# LCD_Character_2x16.net
KiCad netlist of a schematic drawn in Altium Designer
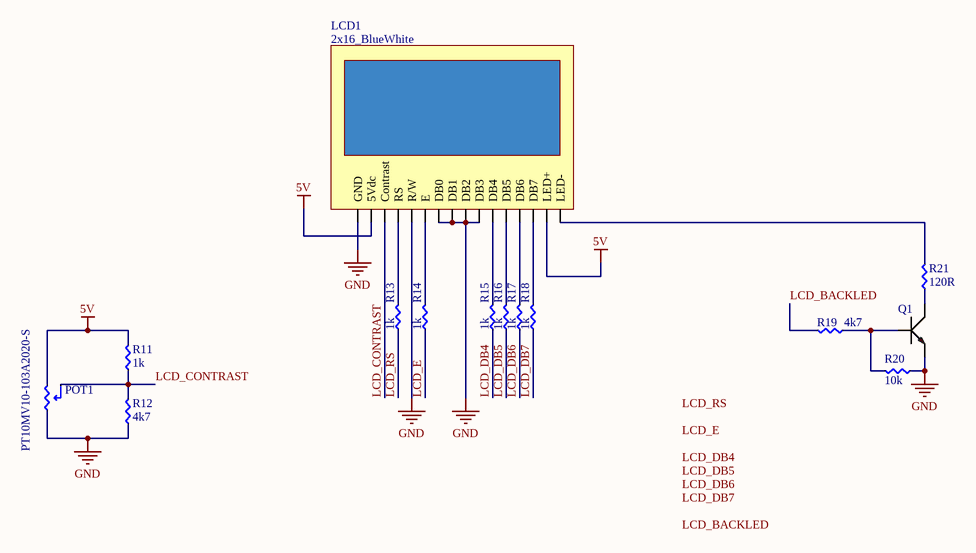
[diagram p0: LCD_Character_2x16.SchDoc]

(export (version "E")
  (design (tool "Eeschema 10.0.6"))
  (components
    (comp (ref "LCD1")
      (value "2x16_BlueWhite")
      (footprint "LCD_2x16_8.4mm")
      (description "LCD MOD CHAR 2X16 WHT TRANSM")
      (fields
        (field (name "MANUFACTURER") "Newhaven Display")
        (field (name "MANUFACTURER PART NUMBER") "NHD-0216K1Z-NSW-BBW-L")
      )
      (libsource (lib "SEMATIK_LIB") (part "NHD-0216K1Z-NSW-BBW-L"))
    )
    (comp (ref "POT1")
      (value "PT10MV10-103A2020-S")
      (footprint "pot_piher_v10")
      (description "POT 10K OHM LINEAR")
      (libsource (lib "SEMATIK_LIB") (part "PT10MV10-103A2020-S"))
    )
    (comp (ref "Q1")
      (value "BC817-25LT1G")
      (footprint "SOT-23")
      (description "TRANS NPN 45V 0.5A SOT23")
      (fields (field (name "MANUFACTURER") "ON Semiconductor") (field (name "BASE PART NUMBER") "BC817"))
      (libsource (lib "SEMATIK_LIB") (part "BC817-25LT1G"))
    )
    (comp (ref "R11")
      (value "1k")
      (footprint "R_0805")
      (description "RES SMD 1K OHM 5% 1/8W 0805")
      (fields (field (name "TOLERANCE") "5%"))
      (libsource (lib "SEMATIK_LIB") (part "RC0805JR-071KL"))
    )
    (comp (ref "R12")
      (value "4k7")
      (footprint "R_0805")
      (description "RES SMD 4.7K OHM 5% 1/8W 0805")
      (fields
        (field (name "MANUFACTURER") "Yageo")
        (field (name "MANUFACTURER PART NUMBER") "RC0805JR-074K7L")
      )
      (libsource (lib "SEMATIK_LIB") (part "RC0805JR-074K7L"))
    )
    (comp (ref "R13")
      (value "1k")
      (footprint "R_0805")
      (description "RES SMD 1K OHM 5% 1/8W 0805")
      (fields (field (name "TOLERANCE") "5%"))
      (libsource (lib "SEMATIK_LIB") (part "RC0805JR-071KL"))
    )
    (comp (ref "R14")
      (value "1k")
      (footprint "R_0805")
      (description "RES SMD 1K OHM 5% 1/8W 0805")
      (fields (field (name "TOLERANCE") "5%"))
      (libsource (lib "SEMATIK_LIB") (part "RC0805JR-071KL"))
    )
    (comp (ref "R15")
      (value "1k")
      (footprint "R_0805")
      (description "RES SMD 1K OHM 5% 1/8W 0805")
      (fields (field (name "TOLERANCE") "5%"))
      (libsource (lib "SEMATIK_LIB") (part "RC0805JR-071KL"))
    )
    (comp (ref "R16")
      (value "1k")
      (footprint "R_0805")
      (description "RES SMD 1K OHM 5% 1/8W 0805")
      (fields (field (name "TOLERANCE") "5%"))
      (libsource (lib "SEMATIK_LIB") (part "RC0805JR-071KL"))
    )
    (comp (ref "R17")
      (value "1k")
      (footprint "R_0805")
      (description "RES SMD 1K OHM 5% 1/8W 0805")
      (fields (field (name "TOLERANCE") "5%"))
      (libsource (lib "SEMATIK_LIB") (part "RC0805JR-071KL"))
    )
    (comp (ref "R18")
      (value "1k")
      (footprint "R_0805")
      (description "RES SMD 1K OHM 5% 1/8W 0805")
      (fields (field (name "TOLERANCE") "5%"))
      (libsource (lib "SEMATIK_LIB") (part "RC0805JR-071KL"))
    )
    (comp (ref "R19")
      (value "4k7")
      (footprint "R_0805")
      (description "RES SMD 4.7K OHM 5% 1/8W 0805")
      (fields
        (field (name "MANUFACTURER") "Yageo")
        (field (name "MANUFACTURER PART NUMBER") "RC0805JR-074K7L")
      )
      (libsource (lib "SEMATIK_LIB") (part "RC0805JR-074K7L"))
    )
    (comp (ref "R20")
      (value "10k")
      (footprint "R_0805")
      (description "RES SMD 10K OHM 5% 1/8W 0805")
      (fields (field (name "TOLERANCE") "5%"))
      (libsource (lib "SEMATIK_LIB") (part "RC0805JR-0710KL"))
    )
    (comp (ref "R21")
      (value "120R")
      (footprint "R_0805")
      (description "RES SMD 120 OHM 1% 1/8W 0805")
      (fields
        (field (name "MANUFACTURER") "Yageo")
        (field (name "MANUFACTURER PART NUMBER") "RC0805FR-07120RL")
      )
      (libsource (lib "SEMATIK_LIB") (part "RC0805FR-07120RL"))
    )
  )
  (nets
    (net (code "1") (name "/LCD_BACKLED") (class "Default")
      (node (ref "R19") (pin "2") (pinfunction "2_2") (pintype "passive"))
    )
    (net (code "2") (name "/LCD_CONTRAST") (class "Default")
      (node (ref "LCD1") (pin "3") (pinfunction "Contrast_3") (pintype "passive"))
      (node (ref "POT1") (pin "3") (pinfunction "3_3") (pintype "passive"))
      (node (ref "R11") (pin "1") (pinfunction "1_1") (pintype "passive"))
      (node (ref "R12") (pin "2") (pinfunction "2_2") (pintype "passive"))
    )
    (net (code "3") (name "/LCD_DB4") (class "Default")
      (node (ref "R15") (pin "1") (pinfunction "1_1") (pintype "passive"))
    )
    (net (code "4") (name "/LCD_DB5") (class "Default")
      (node (ref "R16") (pin "1") (pinfunction "1_1") (pintype "passive"))
    )
    (net (code "5") (name "/LCD_DB6") (class "Default")
      (node (ref "R17") (pin "1") (pinfunction "1_1") (pintype "passive"))
    )
    (net (code "6") (name "/LCD_DB7") (class "Default")
      (node (ref "R18") (pin "1") (pinfunction "1_1") (pintype "passive"))
    )
    (net (code "7") (name "/LCD_E") (class "Default")
      (node (ref "R14") (pin "1") (pinfunction "1_1") (pintype "passive"))
    )
    (net (code "8") (name "/LCD_RS") (class "Default")
      (node (ref "R13") (pin "1") (pinfunction "1_1") (pintype "passive"))
    )
    (net (code "9") (name "5V") (class "Default")
      (node (ref "LCD1") (pin "15") (pinfunction "LED+_15") (pintype "passive"))
      (node (ref "LCD1") (pin "2") (pinfunction "5Vdc_2") (pintype "passive"))
      (node (ref "POT1") (pin "2") (pinfunction "2_2") (pintype "passive"))
      (node (ref "R11") (pin "2") (pinfunction "2_2") (pintype "passive"))
    )
    (net (code "10") (name "GND") (class "Default")
      (node (ref "LCD1") (pin "1") (pinfunction "GND_1") (pintype "passive"))
      (node (ref "LCD1") (pin "10") (pinfunction "DB3_10") (pintype "passive"))
      (node (ref "LCD1") (pin "5") (pinfunction "R/W_5") (pintype "passive"))
      (node (ref "LCD1") (pin "7") (pinfunction "DB0_7") (pintype "passive"))
      (node (ref "LCD1") (pin "8") (pinfunction "DB1_8") (pintype "passive"))
      (node (ref "LCD1") (pin "9") (pinfunction "DB2_9") (pintype "passive"))
      (node (ref "POT1") (pin "1") (pinfunction "1_1") (pintype "passive"))
      (node (ref "Q1") (pin "3") (pinfunction "Emiter_3") (pintype "passive"))
      (node (ref "R12") (pin "1") (pinfunction "1_1") (pintype "passive"))
      (node (ref "R20") (pin "1") (pinfunction "1_1") (pintype "passive"))
    )
    (net (code "11") (name "Net-(LCD1-DB4)") (class "Default")
      (node (ref "LCD1") (pin "11") (pinfunction "DB4_11") (pintype "passive"))
      (node (ref "R15") (pin "2") (pinfunction "2_2") (pintype "passive"))
    )
    (net (code "12") (name "Net-(LCD1-DB5)") (class "Default")
      (node (ref "LCD1") (pin "12") (pinfunction "DB5_12") (pintype "passive"))
      (node (ref "R16") (pin "2") (pinfunction "2_2") (pintype "passive"))
    )
    (net (code "13") (name "Net-(LCD1-DB6)") (class "Default")
      (node (ref "LCD1") (pin "13") (pinfunction "DB6_13") (pintype "passive"))
      (node (ref "R17") (pin "2") (pinfunction "2_2") (pintype "passive"))
    )
    (net (code "14") (name "Net-(LCD1-DB7)") (class "Default")
      (node (ref "LCD1") (pin "14") (pinfunction "DB7_14") (pintype "passive"))
      (node (ref "R18") (pin "2") (pinfunction "2_2") (pintype "passive"))
    )
    (net (code "15") (name "Net-(LCD1-E)") (class "Default")
      (node (ref "LCD1") (pin "6") (pinfunction "E_6") (pintype "passive"))
      (node (ref "R14") (pin "2") (pinfunction "2_2") (pintype "passive"))
    )
    (net (code "16") (name "Net-(LCD1-LED-)") (class "Default")
      (node (ref "LCD1") (pin "16") (pinfunction "LED-_16") (pintype "passive"))
      (node (ref "R21") (pin "2") (pinfunction "2_2") (pintype "passive"))
    )
    (net (code "17") (name "Net-(LCD1-RS)") (class "Default")
      (node (ref "LCD1") (pin "4") (pinfunction "RS_4") (pintype "passive"))
      (node (ref "R13") (pin "2") (pinfunction "2_2") (pintype "passive"))
    )
    (net (code "18") (name "Net-(Q1-Base)") (class "Default")
      (node (ref "Q1") (pin "2") (pinfunction "Base_2") (pintype "passive"))
      (node (ref "R19") (pin "1") (pinfunction "1_1") (pintype "passive"))
      (node (ref "R20") (pin "2") (pinfunction "2_2") (pintype "passive"))
    )
    (net (code "19") (name "Net-(Q1-Collector)") (class "Default")
      (node (ref "Q1") (pin "1") (pinfunction "Collector_1") (pintype "passive"))
      (node (ref "R21") (pin "1") (pinfunction "1_1") (pintype "passive"))
    )
  )
)
